# LED_-_Chaser_Forward_Reverse.net
KiCad netlist of a schematic drawn in EAGLE
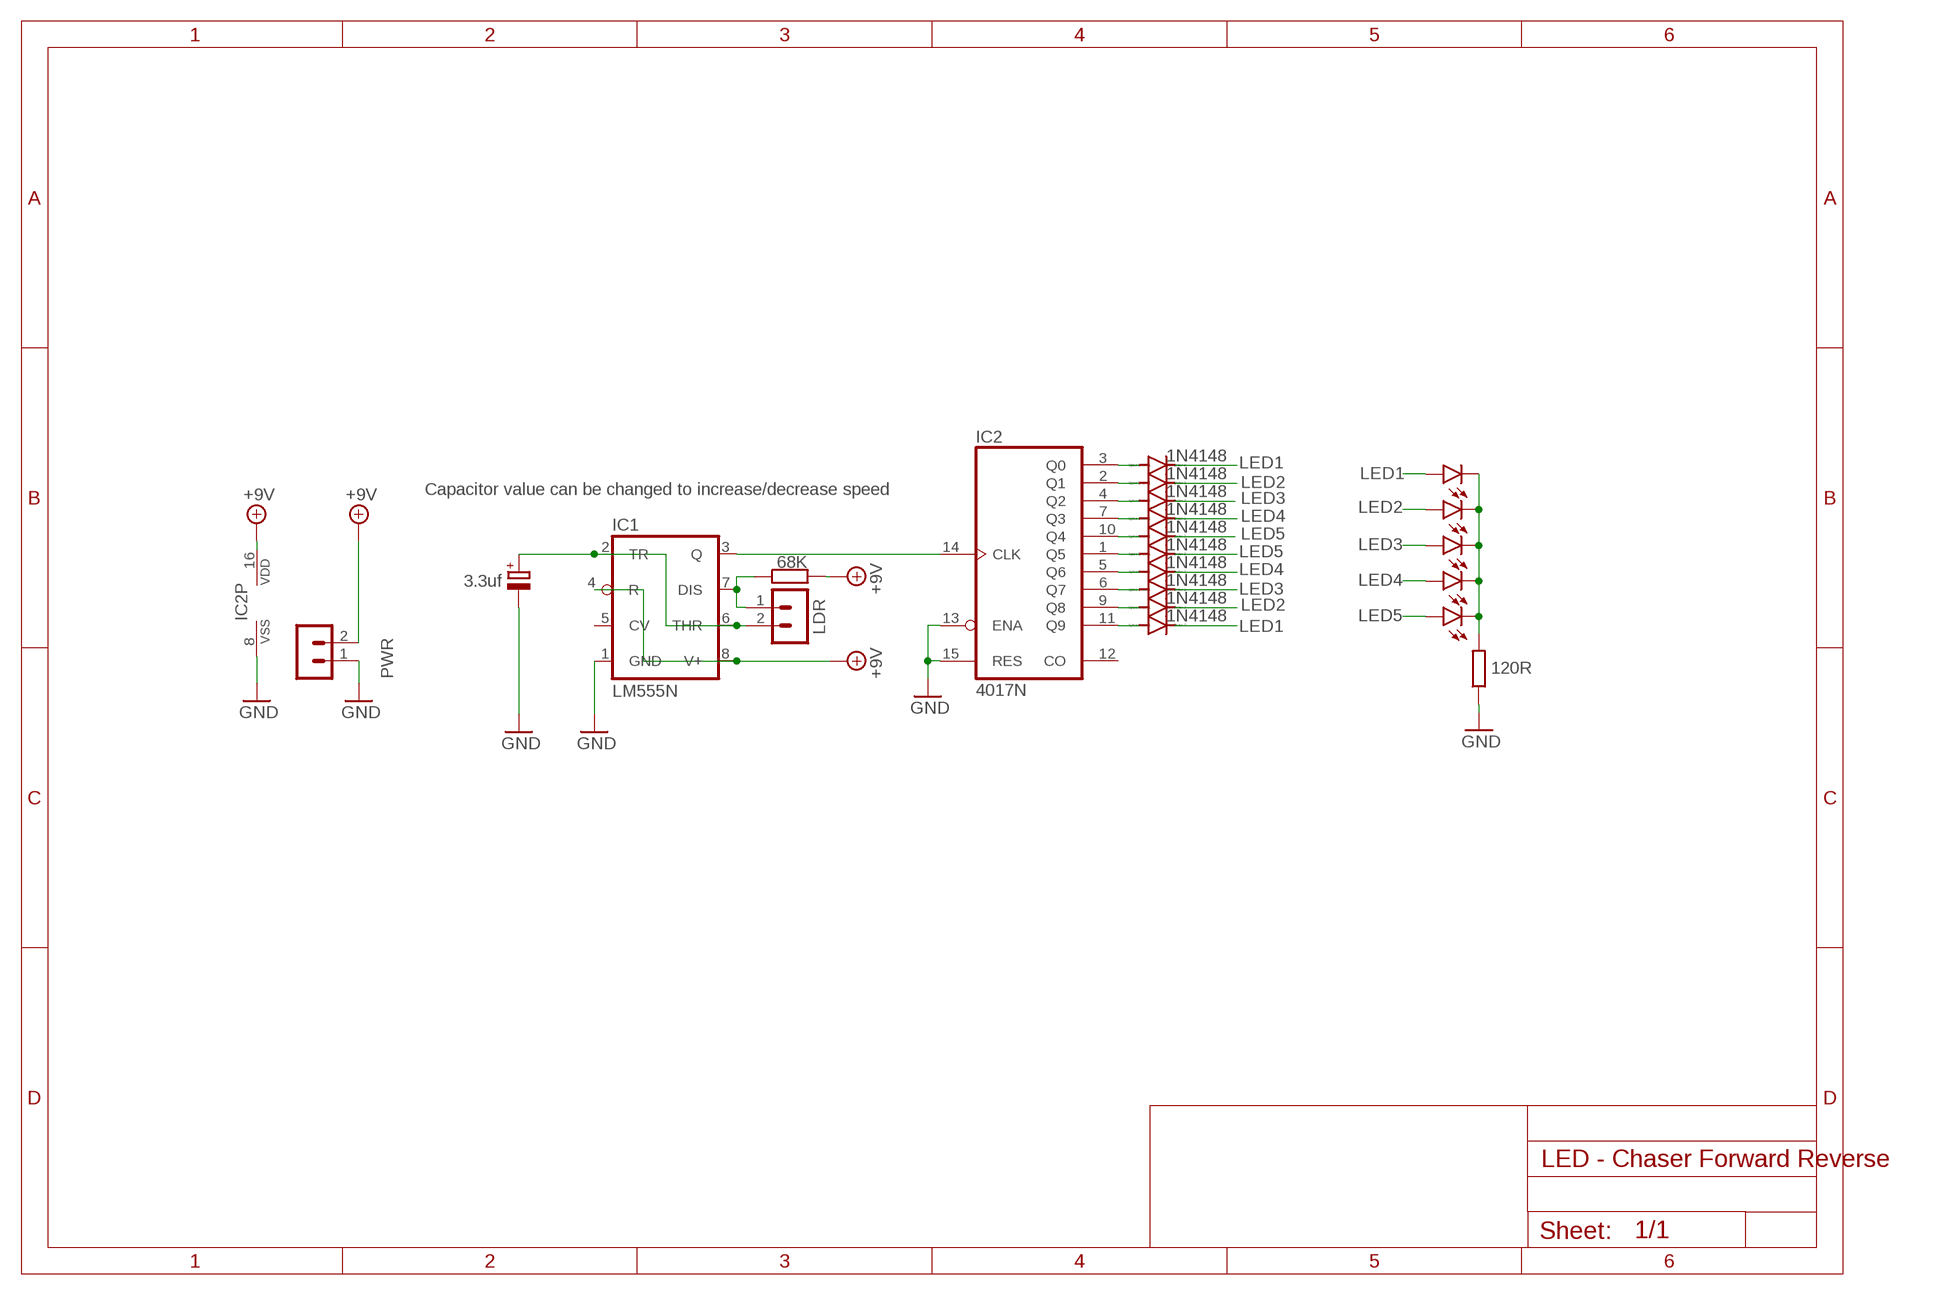
[diagram p0: schematic, sheet 1]

(export (version "E")
  (design (tool "Eeschema 10.0.6"))
  (components
    (comp (ref "C1")
      (value "3.3uf")
      (footprint "eagle-import:E2,5-5")
      (libsource (lib "eagle-import") (part "CPOL-EUE2.5-5"))
    )
    (comp (ref "D1")
      (value "1N4148")
      (footprint "eagle-import:DO35-7")
      (libsource (lib "eagle-import") (part "1N4148DO35-7"))
    )
    (comp (ref "D2")
      (value "1N4148")
      (footprint "eagle-import:DO35-7")
      (libsource (lib "eagle-import") (part "1N4148DO35-7"))
    )
    (comp (ref "D3")
      (value "1N4148")
      (footprint "eagle-import:DO35-7")
      (libsource (lib "eagle-import") (part "1N4148DO35-7"))
    )
    (comp (ref "D4")
      (value "1N4148")
      (footprint "eagle-import:DO35-7")
      (libsource (lib "eagle-import") (part "1N4148DO35-7"))
    )
    (comp (ref "D5")
      (value "1N4148")
      (footprint "eagle-import:DO35-7")
      (libsource (lib "eagle-import") (part "1N4148DO35-7"))
    )
    (comp (ref "D6")
      (value "1N4148")
      (footprint "eagle-import:DO35-7")
      (libsource (lib "eagle-import") (part "1N4148DO35-7"))
    )
    (comp (ref "D7")
      (value "1N4148")
      (footprint "eagle-import:DO35-7")
      (libsource (lib "eagle-import") (part "1N4148DO35-7"))
    )
    (comp (ref "D8")
      (value "1N4148")
      (footprint "eagle-import:DO35-7")
      (libsource (lib "eagle-import") (part "1N4148DO35-7"))
    )
    (comp (ref "D9")
      (value "1N4148")
      (footprint "eagle-import:DO35-7")
      (libsource (lib "eagle-import") (part "1N4148DO35-7"))
    )
    (comp (ref "D10")
      (value "1N4148")
      (footprint "eagle-import:DO35-7")
      (libsource (lib "eagle-import") (part "1N4148DO35-7"))
    )
    (comp (ref "IC1")
      (value "LM555N")
      (footprint "eagle-import:DIL08")
      (libsource (lib "eagle-import") (part "555NLM"))
    )
    (comp (ref "IC2")
      (value "4017N")
      (footprint "eagle-import:DIL16")
      (libsource (lib "eagle-import") (part "4017N"))
    )
    (comp (ref "LDR")
      (value "B2B-PH-K-S")
      (footprint "eagle-import:B2B-PH-K-S")
      (libsource (lib "eagle-import") (part "B2B-PH-K-S"))
    )
    (comp (ref "LED1")
      (value "LED3MM")
      (footprint "eagle-import:LED3MM")
      (libsource (lib "eagle-import") (part "LED3MM"))
    )
    (comp (ref "LED2")
      (value "LED3MM")
      (footprint "eagle-import:LED3MM")
      (libsource (lib "eagle-import") (part "LED3MM"))
    )
    (comp (ref "LED3")
      (value "LED3MM")
      (footprint "eagle-import:LED3MM")
      (libsource (lib "eagle-import") (part "LED3MM"))
    )
    (comp (ref "LED4")
      (value "LED3MM")
      (footprint "eagle-import:LED3MM")
      (libsource (lib "eagle-import") (part "LED3MM"))
    )
    (comp (ref "LED5")
      (value "LED3MM")
      (footprint "eagle-import:LED3MM")
      (libsource (lib "eagle-import") (part "LED3MM"))
    )
    (comp (ref "PWR")
      (value "B2B-PH-K-S")
      (footprint "eagle-import:B2B-PH-K-S")
      (libsource (lib "eagle-import") (part "B2B-PH-K-S"))
    )
    (comp (ref "R1")
      (value "68K")
      (footprint "eagle-import:0207_10")
      (libsource (lib "eagle-import") (part "R-EU_0207/10"))
    )
    (comp (ref "R2")
      (value "120R")
      (footprint "eagle-import:0207_10")
      (libsource (lib "eagle-import") (part "R-EU_0207/10"))
    )
  )
  (nets
    (net (code "1") (name "+9V") (class "Default")
      (node (ref "IC1") (pin "4") (pinfunction "R_4") (pintype "input"))
      (node (ref "IC1") (pin "8") (pinfunction "V+_8") (pintype "power_in"))
      (node (ref "IC2") (pin "16") (pinfunction "VDD_16") (pintype "power_in"))
      (node (ref "PWR") (pin "2") (pinfunction "2_2") (pintype "passive"))
      (node (ref "R1") (pin "2") (pinfunction "2_2") (pintype "passive"))
    )
    (net (code "2") (name "/LED1") (class "Default")
      (node (ref "D1") (pin "C") (pinfunction "C_C") (pintype "passive"))
      (node (ref "D10") (pin "C") (pinfunction "C_C") (pintype "passive"))
      (node (ref "LED1") (pin "A") (pinfunction "A_A") (pintype "passive"))
    )
    (net (code "3") (name "/LED2") (class "Default")
      (node (ref "D2") (pin "C") (pinfunction "C_C") (pintype "passive"))
      (node (ref "D9") (pin "C") (pinfunction "C_C") (pintype "passive"))
      (node (ref "LED2") (pin "A") (pinfunction "A_A") (pintype "passive"))
    )
    (net (code "4") (name "/LED3") (class "Default")
      (node (ref "D3") (pin "C") (pinfunction "C_C") (pintype "passive"))
      (node (ref "D8") (pin "C") (pinfunction "C_C") (pintype "passive"))
      (node (ref "LED3") (pin "A") (pinfunction "A_A") (pintype "passive"))
    )
    (net (code "5") (name "/LED4") (class "Default")
      (node (ref "D4") (pin "C") (pinfunction "C_C") (pintype "passive"))
      (node (ref "D7") (pin "C") (pinfunction "C_C") (pintype "passive"))
      (node (ref "LED4") (pin "A") (pinfunction "A_A") (pintype "passive"))
    )
    (net (code "6") (name "/LED5") (class "Default")
      (node (ref "D5") (pin "C") (pinfunction "C_C") (pintype "passive"))
      (node (ref "D6") (pin "C") (pinfunction "C_C") (pintype "passive"))
      (node (ref "LED5") (pin "A") (pinfunction "A_A") (pintype "passive"))
    )
    (net (code "7") (name "GND") (class "Default")
      (node (ref "C1") (pin "-") (pinfunction "-_-") (pintype "passive"))
      (node (ref "IC1") (pin "1") (pinfunction "GND_1") (pintype "power_in"))
      (node (ref "IC2") (pin "13") (pinfunction "ENA_13") (pintype "input"))
      (node (ref "IC2") (pin "15") (pinfunction "RES_15") (pintype "input"))
      (node (ref "IC2") (pin "8") (pinfunction "VSS_8") (pintype "power_in"))
      (node (ref "PWR") (pin "1") (pinfunction "1_1") (pintype "passive"))
      (node (ref "R2") (pin "1") (pinfunction "1_1") (pintype "passive"))
    )
    (net (code "8") (name "Net-(IC1-DIS)") (class "Default")
      (node (ref "IC1") (pin "7") (pinfunction "DIS_7") (pintype "input"))
      (node (ref "LDR") (pin "1") (pinfunction "1_1") (pintype "passive"))
      (node (ref "R1") (pin "1") (pinfunction "1_1") (pintype "passive"))
    )
    (net (code "9") (name "Net-(IC1-Q)") (class "Default")
      (node (ref "IC1") (pin "3") (pinfunction "Q_3") (pintype "output"))
      (node (ref "IC2") (pin "14") (pinfunction "CLK_14") (pintype "input"))
    )
    (net (code "10") (name "Net-(IC1-THR)") (class "Default")
      (node (ref "C1") (pin "+") (pinfunction "+_+") (pintype "passive"))
      (node (ref "IC1") (pin "2") (pinfunction "TR_2") (pintype "input"))
      (node (ref "IC1") (pin "6") (pinfunction "THR_6") (pintype "input"))
      (node (ref "LDR") (pin "2") (pinfunction "2_2") (pintype "passive"))
    )
    (net (code "11") (name "Net-(IC2A-Q0)") (class "Default")
      (node (ref "D1") (pin "A") (pinfunction "A_A") (pintype "passive"))
      (node (ref "IC2") (pin "3") (pinfunction "Q0_3") (pintype "output"))
    )
    (net (code "12") (name "Net-(IC2A-Q1)") (class "Default")
      (node (ref "D2") (pin "A") (pinfunction "A_A") (pintype "passive"))
      (node (ref "IC2") (pin "2") (pinfunction "Q1_2") (pintype "output"))
    )
    (net (code "13") (name "Net-(IC2A-Q2)") (class "Default")
      (node (ref "D3") (pin "A") (pinfunction "A_A") (pintype "passive"))
      (node (ref "IC2") (pin "4") (pinfunction "Q2_4") (pintype "output"))
    )
    (net (code "14") (name "Net-(IC2A-Q3)") (class "Default")
      (node (ref "D4") (pin "A") (pinfunction "A_A") (pintype "passive"))
      (node (ref "IC2") (pin "7") (pinfunction "Q3_7") (pintype "output"))
    )
    (net (code "15") (name "Net-(IC2A-Q4)") (class "Default")
      (node (ref "D5") (pin "A") (pinfunction "A_A") (pintype "passive"))
      (node (ref "IC2") (pin "10") (pinfunction "Q4_10") (pintype "output"))
    )
    (net (code "16") (name "Net-(IC2A-Q5)") (class "Default")
      (node (ref "D6") (pin "A") (pinfunction "A_A") (pintype "passive"))
      (node (ref "IC2") (pin "1") (pinfunction "Q5_1") (pintype "output"))
    )
    (net (code "17") (name "Net-(IC2A-Q6)") (class "Default")
      (node (ref "D7") (pin "A") (pinfunction "A_A") (pintype "passive"))
      (node (ref "IC2") (pin "5") (pinfunction "Q6_5") (pintype "output"))
    )
    (net (code "18") (name "Net-(IC2A-Q7)") (class "Default")
      (node (ref "D8") (pin "A") (pinfunction "A_A") (pintype "passive"))
      (node (ref "IC2") (pin "6") (pinfunction "Q7_6") (pintype "output"))
    )
    (net (code "19") (name "Net-(IC2A-Q8)") (class "Default")
      (node (ref "D9") (pin "A") (pinfunction "A_A") (pintype "passive"))
      (node (ref "IC2") (pin "9") (pinfunction "Q8_9") (pintype "output"))
    )
    (net (code "20") (name "Net-(IC2A-Q9)") (class "Default")
      (node (ref "D10") (pin "A") (pinfunction "A_A") (pintype "passive"))
      (node (ref "IC2") (pin "11") (pinfunction "Q9_11") (pintype "output"))
    )
    (net (code "21") (name "Net-(LED1-C)") (class "Default")
      (node (ref "LED1") (pin "K") (pinfunction "C_K") (pintype "passive"))
      (node (ref "LED2") (pin "K") (pinfunction "C_K") (pintype "passive"))
      (node (ref "LED3") (pin "K") (pinfunction "C_K") (pintype "passive"))
      (node (ref "LED4") (pin "K") (pinfunction "C_K") (pintype "passive"))
      (node (ref "LED5") (pin "K") (pinfunction "C_K") (pintype "passive"))
      (node (ref "R2") (pin "2") (pinfunction "2_2") (pintype "passive"))
    )
    (net (code "22") (name "unconnected-(IC1-CV-Pad5)") (class "Default")
      (node (ref "IC1") (pin "5") (pinfunction "CV_5") (pintype "input"))
    )
    (net (code "23") (name "unconnected-(IC2A-CO-Pad12)") (class "Default")
      (node (ref "IC2") (pin "12") (pinfunction "CO_12") (pintype "output"))
    )
  )
)
